# Bumper_coil.net
KiCad netlist of a schematic drawn in EAGLE
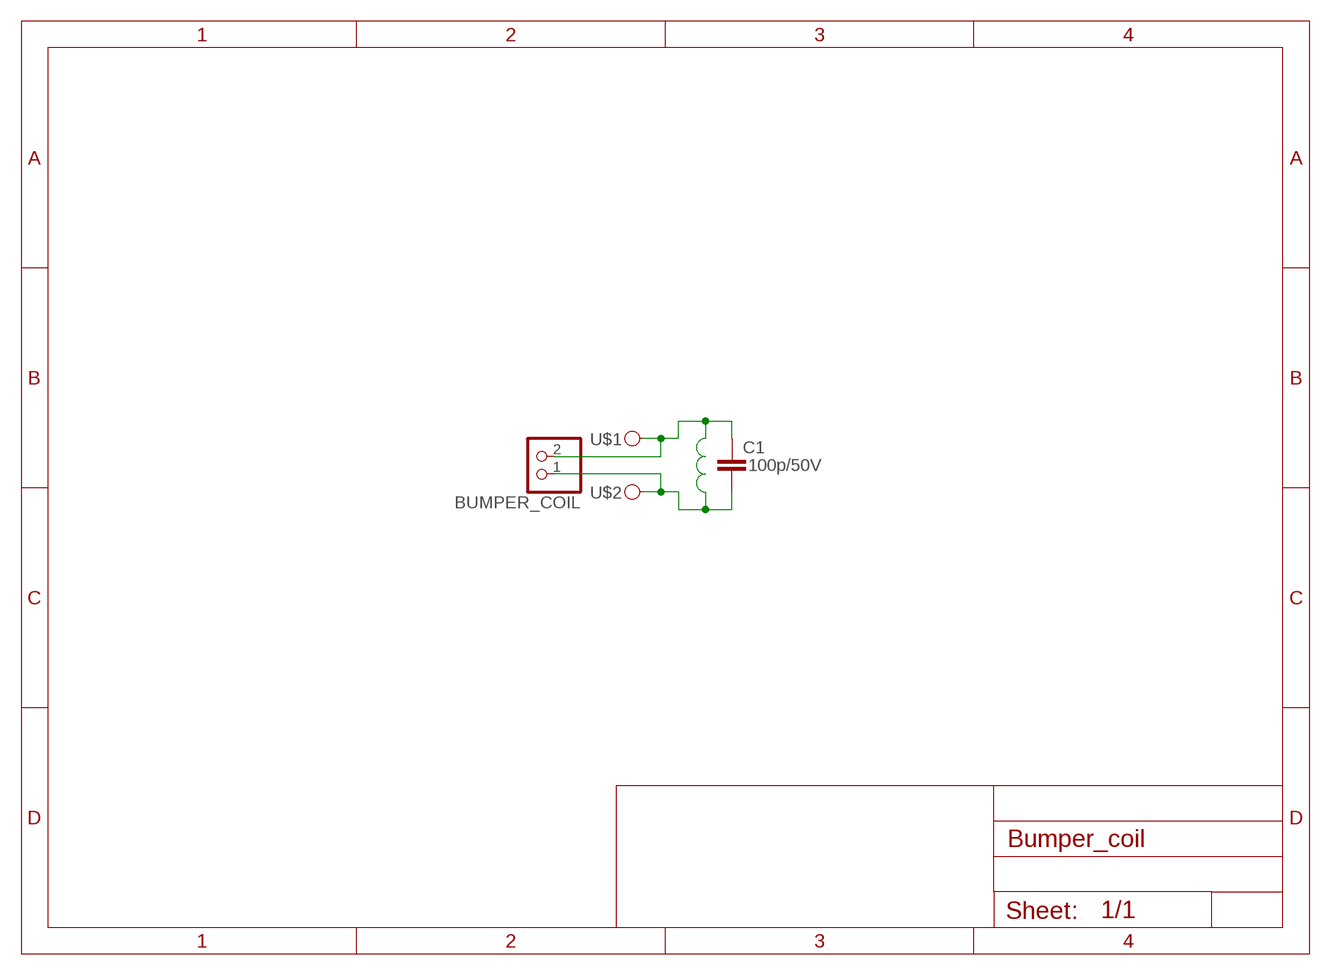
[diagram p0: schematic, sheet 1]

(export (version "E")
  (design (tool "Eeschema 10.0.6"))
  (components
    (comp (ref "BUMPER_COIL")
      (value "PINHD-1X2/90")
      (footprint "eagle-import:1X02_90")
      (libsource (lib "eagle-import") (part "PINHD-1X2/90"))
    )
    (comp (ref "C1")
      (value "100p/50V")
      (footprint "eagle-import:C0402")
      (libsource (lib "eagle-import") (part "C-EUC0402"))
    )
    (comp (ref "U$1")
      (value "PINHEAD_SMD_1X1")
      (footprint "eagle-import:PINHEAD_SMD_1X1")
      (libsource (lib "eagle-import") (part "PINHEAD_SMD_1X1"))
    )
    (comp (ref "U$2")
      (value "PINHEAD_SMD_1X1")
      (footprint "eagle-import:PINHEAD_SMD_1X1")
      (libsource (lib "eagle-import") (part "PINHEAD_SMD_1X1"))
    )
  )
  (nets
    (net (code "1") (name "/COIL0") (class "Default")
      (node (ref "BUMPER_COIL") (pin "1") (pinfunction "1_1") (pintype "passive"))
      (node (ref "BUMPER_COIL") (pin "2") (pinfunction "2_2") (pintype "passive"))
      (node (ref "C1") (pin "1") (pinfunction "1_1") (pintype "passive"))
      (node (ref "C1") (pin "2") (pinfunction "2_2") (pintype "passive"))
      (node (ref "U$1") (pin "1") (pinfunction "1_1") (pintype "passive"))
      (node (ref "U$2") (pin "1") (pinfunction "1_1") (pintype "passive"))
    )
  )
)
